# Magnetometer.net
KiCad netlist of a schematic drawn in Altium Designer
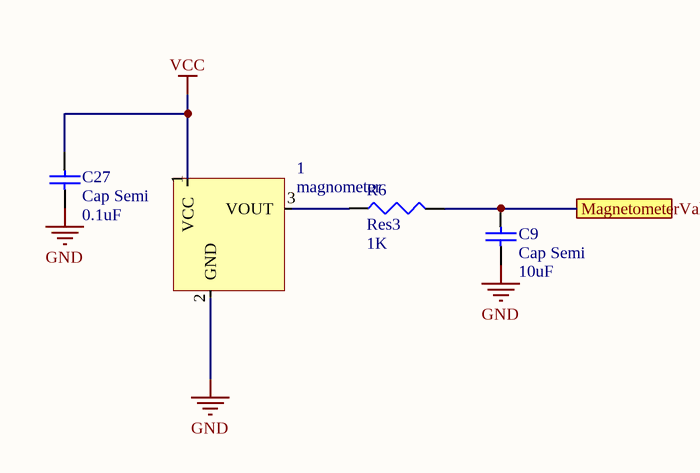
[diagram p0: Magnetometer.SchDoc]

(export (version "E")
  (design (tool "Eeschema 10.0.6"))
  (components
    (comp (ref "1")
      (value "magnometer")
      (footprint "SIP-3")
      (libsource (lib "HGCDLibrary") (part "magnometer"))
    )
    (comp (ref "C9")
      (value "Cap Semi")
      (footprint "1608[0603]")
      (description "Capacitor (Semiconductor SIM Model)")
      (fields (field (name "ALTIUM_VALUE") "10uF") (field (name "PUBLISHER") "Altium Limited"))
      (libsource (lib "Miscellaneous Devices") (part "Cap Semi"))
    )
    (comp (ref "C27")
      (value "Cap Semi")
      (footprint "1608[0603]")
      (description "Capacitor (Semiconductor SIM Model)")
      (fields (field (name "ALTIUM_VALUE") "0.1uF") (field (name "PUBLISHER") "Altium Limited"))
      (libsource (lib "Miscellaneous Devices") (part "Cap Semi"))
    )
    (comp (ref "R6")
      (value "Res3")
      (footprint "J1-0603")
      (description "Resistor")
      (fields (field (name "ALTIUM_VALUE") "1K") (field (name "PUBLISHER") "Altium Limited"))
      (libsource (lib "Miscellaneous Devices") (part "Res3"))
    )
  )
  (nets
    (net (code "1") (name "/MagnetometerVal") (class "Default")
      (node (ref "C9") (pin "2") (pinfunction "2_2") (pintype "passive"))
      (node (ref "R6") (pin "2") (pinfunction "2_2") (pintype "passive"))
    )
    (net (code "2") (name "GND") (class "Default")
      (node (ref "1") (pin "2") (pinfunction "GND_2") (pintype "power_in"))
      (node (ref "C27") (pin "1") (pinfunction "1_1") (pintype "passive"))
      (node (ref "C9") (pin "1") (pinfunction "1_1") (pintype "passive"))
    )
    (net (code "3") (name "Net-(1-VOUT)") (class "Default")
      (node (ref "1") (pin "3") (pinfunction "VOUT_3") (pintype "output"))
      (node (ref "R6") (pin "1") (pinfunction "1_1") (pintype "passive"))
    )
    (net (code "4") (name "VCC") (class "Default")
      (node (ref "1") (pin "1") (pinfunction "VCC_1") (pintype "power_in"))
      (node (ref "C27") (pin "2") (pinfunction "2_2") (pintype "passive"))
    )
  )
)
